# 20_Torq.net
KiCad netlist of a schematic drawn in Altium Designer
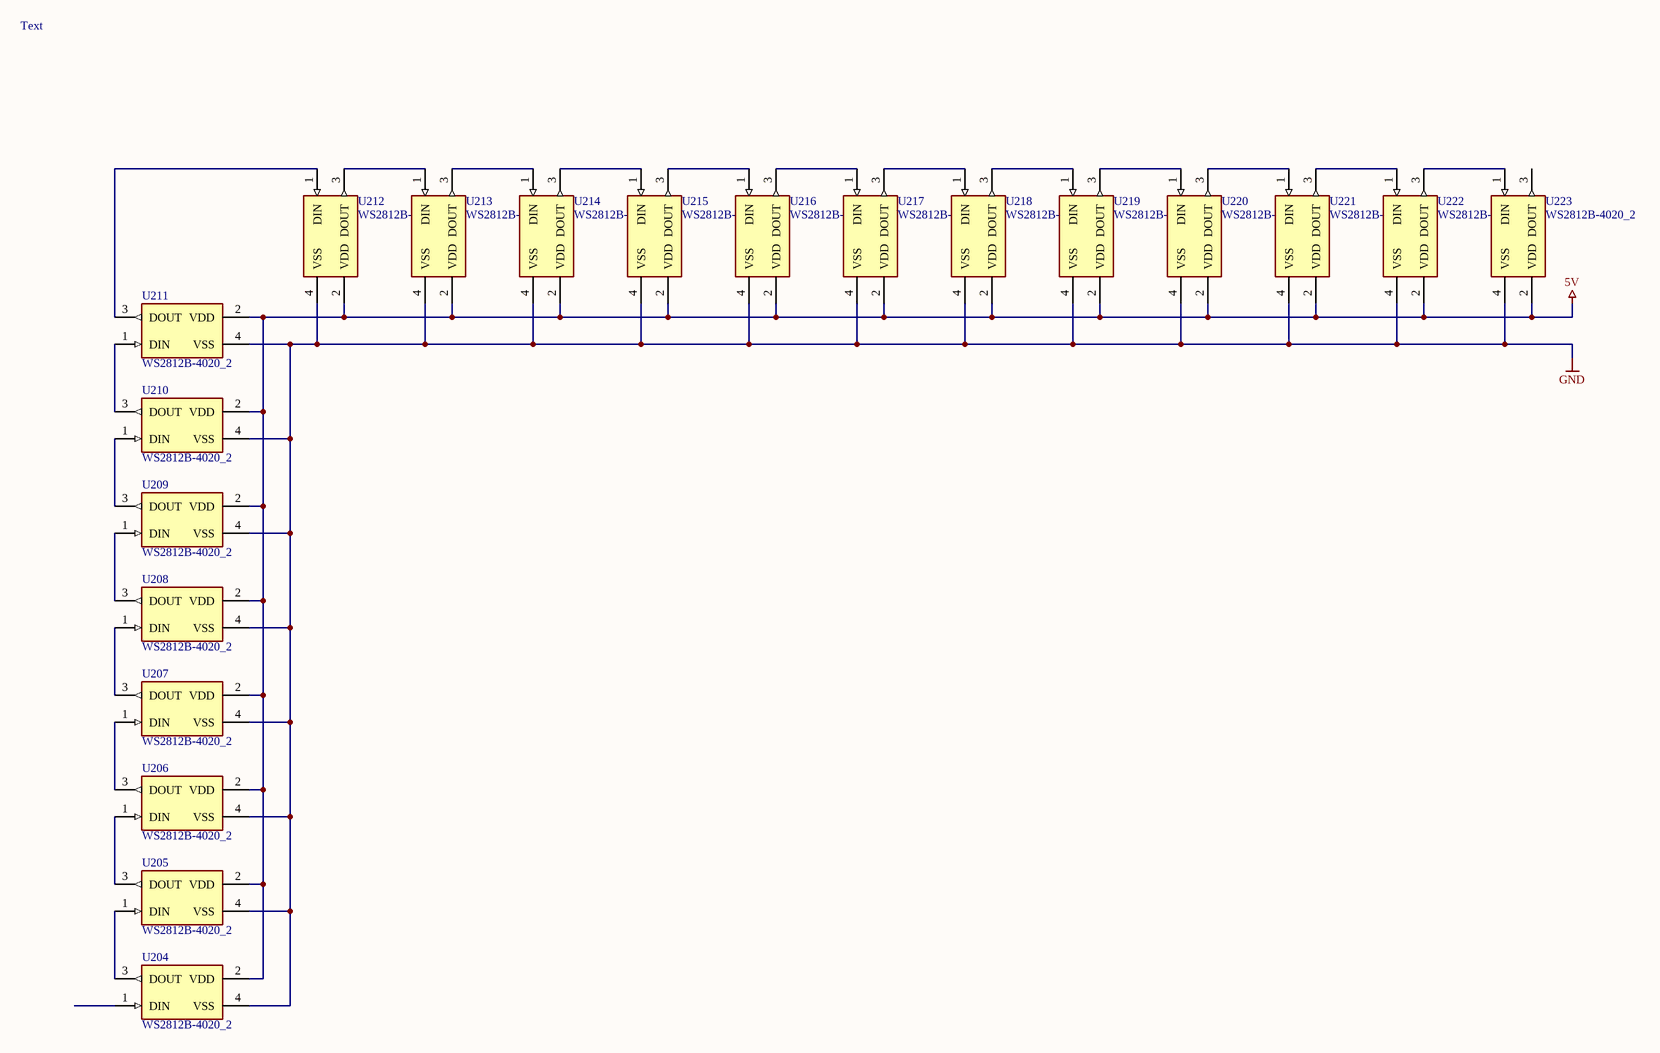
[diagram p0: 20_Torq.SchDoc]

(export (version "E")
  (design (tool "Eeschema 10.0.6"))
  (components
    (comp (ref "U204")
      (value "WS2812B-4020_2")
      (footprint "LED_WS2812B-4020")
      (description "12mA RGB SMD,2x4mm Light Emitting Diodes")
      (fields (field (name "MP") "WS2812B-4020") (field (name "MF") "Worldsemi"))
      (libsource (lib "AltiumLib_MILUTIN") (part "WS2812B-4020_2"))
    )
    (comp (ref "U205")
      (value "WS2812B-4020_2")
      (footprint "LED_WS2812B-4020")
      (description "12mA RGB SMD,2x4mm Light Emitting Diodes")
      (fields (field (name "MP") "WS2812B-4020") (field (name "MF") "Worldsemi"))
      (libsource (lib "AltiumLib_MILUTIN") (part "WS2812B-4020_2"))
    )
    (comp (ref "U206")
      (value "WS2812B-4020_2")
      (footprint "LED_WS2812B-4020")
      (description "12mA RGB SMD,2x4mm Light Emitting Diodes")
      (fields (field (name "MP") "WS2812B-4020") (field (name "MF") "Worldsemi"))
      (libsource (lib "AltiumLib_MILUTIN") (part "WS2812B-4020_2"))
    )
    (comp (ref "U207")
      (value "WS2812B-4020_2")
      (footprint "LED_WS2812B-4020")
      (description "12mA RGB SMD,2x4mm Light Emitting Diodes")
      (fields (field (name "MP") "WS2812B-4020") (field (name "MF") "Worldsemi"))
      (libsource (lib "AltiumLib_MILUTIN") (part "WS2812B-4020_2"))
    )
    (comp (ref "U208")
      (value "WS2812B-4020_2")
      (footprint "LED_WS2812B-4020")
      (description "12mA RGB SMD,2x4mm Light Emitting Diodes")
      (fields (field (name "MP") "WS2812B-4020") (field (name "MF") "Worldsemi"))
      (libsource (lib "AltiumLib_MILUTIN") (part "WS2812B-4020_2"))
    )
    (comp (ref "U209")
      (value "WS2812B-4020_2")
      (footprint "LED_WS2812B-4020")
      (description "12mA RGB SMD,2x4mm Light Emitting Diodes")
      (fields (field (name "MP") "WS2812B-4020") (field (name "MF") "Worldsemi"))
      (libsource (lib "AltiumLib_MILUTIN") (part "WS2812B-4020_2"))
    )
    (comp (ref "U210")
      (value "WS2812B-4020_2")
      (footprint "LED_WS2812B-4020")
      (description "12mA RGB SMD,2x4mm Light Emitting Diodes")
      (fields (field (name "MP") "WS2812B-4020") (field (name "MF") "Worldsemi"))
      (libsource (lib "AltiumLib_MILUTIN") (part "WS2812B-4020_2"))
    )
    (comp (ref "U211")
      (value "WS2812B-4020_2")
      (footprint "LED_WS2812B-4020")
      (description "12mA RGB SMD,2x4mm Light Emitting Diodes")
      (fields (field (name "MP") "WS2812B-4020") (field (name "MF") "Worldsemi"))
      (libsource (lib "AltiumLib_MILUTIN") (part "WS2812B-4020_2"))
    )
    (comp (ref "U212")
      (value "WS2812B-4020_2")
      (footprint "LED_WS2812B-4020")
      (description "12mA RGB SMD,2x4mm Light Emitting Diodes")
      (fields (field (name "MP") "WS2812B-4020") (field (name "MF") "Worldsemi"))
      (libsource (lib "") (part "WS2812B-4020_2_1"))
    )
    (comp (ref "U213")
      (value "WS2812B-4020_2")
      (footprint "LED_WS2812B-4020")
      (description "12mA RGB SMD,2x4mm Light Emitting Diodes")
      (fields (field (name "MP") "WS2812B-4020") (field (name "MF") "Worldsemi"))
      (libsource (lib "") (part "WS2812B-4020_2_1"))
    )
    (comp (ref "U214")
      (value "WS2812B-4020_2")
      (footprint "LED_WS2812B-4020")
      (description "12mA RGB SMD,2x4mm Light Emitting Diodes")
      (fields (field (name "MP") "WS2812B-4020") (field (name "MF") "Worldsemi"))
      (libsource (lib "") (part "WS2812B-4020_2_1"))
    )
    (comp (ref "U215")
      (value "WS2812B-4020_2")
      (footprint "LED_WS2812B-4020")
      (description "12mA RGB SMD,2x4mm Light Emitting Diodes")
      (fields (field (name "MP") "WS2812B-4020") (field (name "MF") "Worldsemi"))
      (libsource (lib "") (part "WS2812B-4020_2_1"))
    )
    (comp (ref "U216")
      (value "WS2812B-4020_2")
      (footprint "LED_WS2812B-4020")
      (description "12mA RGB SMD,2x4mm Light Emitting Diodes")
      (fields (field (name "MP") "WS2812B-4020") (field (name "MF") "Worldsemi"))
      (libsource (lib "") (part "WS2812B-4020_2_1"))
    )
    (comp (ref "U217")
      (value "WS2812B-4020_2")
      (footprint "LED_WS2812B-4020")
      (description "12mA RGB SMD,2x4mm Light Emitting Diodes")
      (fields (field (name "MP") "WS2812B-4020") (field (name "MF") "Worldsemi"))
      (libsource (lib "") (part "WS2812B-4020_2_1"))
    )
    (comp (ref "U218")
      (value "WS2812B-4020_2")
      (footprint "LED_WS2812B-4020")
      (description "12mA RGB SMD,2x4mm Light Emitting Diodes")
      (fields (field (name "MP") "WS2812B-4020") (field (name "MF") "Worldsemi"))
      (libsource (lib "") (part "WS2812B-4020_2_1"))
    )
    (comp (ref "U219")
      (value "WS2812B-4020_2")
      (footprint "LED_WS2812B-4020")
      (description "12mA RGB SMD,2x4mm Light Emitting Diodes")
      (fields (field (name "MP") "WS2812B-4020") (field (name "MF") "Worldsemi"))
      (libsource (lib "") (part "WS2812B-4020_2_1"))
    )
    (comp (ref "U220")
      (value "WS2812B-4020_2")
      (footprint "LED_WS2812B-4020")
      (description "12mA RGB SMD,2x4mm Light Emitting Diodes")
      (fields (field (name "MP") "WS2812B-4020") (field (name "MF") "Worldsemi"))
      (libsource (lib "") (part "WS2812B-4020_2_1"))
    )
    (comp (ref "U221")
      (value "WS2812B-4020_2")
      (footprint "LED_WS2812B-4020")
      (description "12mA RGB SMD,2x4mm Light Emitting Diodes")
      (fields (field (name "MP") "WS2812B-4020") (field (name "MF") "Worldsemi"))
      (libsource (lib "") (part "WS2812B-4020_2_1"))
    )
    (comp (ref "U222")
      (value "WS2812B-4020_2")
      (footprint "LED_WS2812B-4020")
      (description "12mA RGB SMD,2x4mm Light Emitting Diodes")
      (fields (field (name "MP") "WS2812B-4020") (field (name "MF") "Worldsemi"))
      (libsource (lib "") (part "WS2812B-4020_2_1"))
    )
    (comp (ref "U223")
      (value "WS2812B-4020_2")
      (footprint "LED_WS2812B-4020")
      (description "12mA RGB SMD,2x4mm Light Emitting Diodes")
      (fields (field (name "MP") "WS2812B-4020") (field (name "MF") "Worldsemi"))
      (libsource (lib "") (part "WS2812B-4020_2_1"))
    )
  )
  (nets
    (net (code "1") (name "5V") (class "Default")
      (node (ref "U204") (pin "2") (pinfunction "VDD_2") (pintype "power_in"))
      (node (ref "U205") (pin "2") (pinfunction "VDD_2") (pintype "power_in"))
      (node (ref "U206") (pin "2") (pinfunction "VDD_2") (pintype "power_in"))
      (node (ref "U207") (pin "2") (pinfunction "VDD_2") (pintype "power_in"))
      (node (ref "U208") (pin "2") (pinfunction "VDD_2") (pintype "power_in"))
      (node (ref "U209") (pin "2") (pinfunction "VDD_2") (pintype "power_in"))
      (node (ref "U210") (pin "2") (pinfunction "VDD_2") (pintype "power_in"))
      (node (ref "U211") (pin "2") (pinfunction "VDD_2") (pintype "power_in"))
      (node (ref "U212") (pin "2") (pinfunction "VDD_2") (pintype "power_in"))
      (node (ref "U213") (pin "2") (pinfunction "VDD_2") (pintype "power_in"))
      (node (ref "U214") (pin "2") (pinfunction "VDD_2") (pintype "power_in"))
      (node (ref "U215") (pin "2") (pinfunction "VDD_2") (pintype "power_in"))
      (node (ref "U216") (pin "2") (pinfunction "VDD_2") (pintype "power_in"))
      (node (ref "U217") (pin "2") (pinfunction "VDD_2") (pintype "power_in"))
      (node (ref "U218") (pin "2") (pinfunction "VDD_2") (pintype "power_in"))
      (node (ref "U219") (pin "2") (pinfunction "VDD_2") (pintype "power_in"))
      (node (ref "U220") (pin "2") (pinfunction "VDD_2") (pintype "power_in"))
      (node (ref "U221") (pin "2") (pinfunction "VDD_2") (pintype "power_in"))
      (node (ref "U222") (pin "2") (pinfunction "VDD_2") (pintype "power_in"))
      (node (ref "U223") (pin "2") (pinfunction "VDD_2") (pintype "power_in"))
    )
    (net (code "2") (name "GND") (class "Default")
      (node (ref "U204") (pin "4") (pinfunction "VSS_4") (pintype "power_in"))
      (node (ref "U205") (pin "4") (pinfunction "VSS_4") (pintype "power_in"))
      (node (ref "U206") (pin "4") (pinfunction "VSS_4") (pintype "power_in"))
      (node (ref "U207") (pin "4") (pinfunction "VSS_4") (pintype "power_in"))
      (node (ref "U208") (pin "4") (pinfunction "VSS_4") (pintype "power_in"))
      (node (ref "U209") (pin "4") (pinfunction "VSS_4") (pintype "power_in"))
      (node (ref "U210") (pin "4") (pinfunction "VSS_4") (pintype "power_in"))
      (node (ref "U211") (pin "4") (pinfunction "VSS_4") (pintype "power_in"))
      (node (ref "U212") (pin "4") (pinfunction "VSS_4") (pintype "power_in"))
      (node (ref "U213") (pin "4") (pinfunction "VSS_4") (pintype "power_in"))
      (node (ref "U214") (pin "4") (pinfunction "VSS_4") (pintype "power_in"))
      (node (ref "U215") (pin "4") (pinfunction "VSS_4") (pintype "power_in"))
      (node (ref "U216") (pin "4") (pinfunction "VSS_4") (pintype "power_in"))
      (node (ref "U217") (pin "4") (pinfunction "VSS_4") (pintype "power_in"))
      (node (ref "U218") (pin "4") (pinfunction "VSS_4") (pintype "power_in"))
      (node (ref "U219") (pin "4") (pinfunction "VSS_4") (pintype "power_in"))
      (node (ref "U220") (pin "4") (pinfunction "VSS_4") (pintype "power_in"))
      (node (ref "U221") (pin "4") (pinfunction "VSS_4") (pintype "power_in"))
      (node (ref "U222") (pin "4") (pinfunction "VSS_4") (pintype "power_in"))
      (node (ref "U223") (pin "4") (pinfunction "VSS_4") (pintype "power_in"))
    )
    (net (code "3") (name "Net-(U204-DOUT)") (class "Default")
      (node (ref "U204") (pin "3") (pinfunction "DOUT_3") (pintype "output"))
      (node (ref "U205") (pin "1") (pinfunction "DIN_1") (pintype "input"))
    )
    (net (code "4") (name "Net-(U205-DOUT)") (class "Default")
      (node (ref "U205") (pin "3") (pinfunction "DOUT_3") (pintype "output"))
      (node (ref "U206") (pin "1") (pinfunction "DIN_1") (pintype "input"))
    )
    (net (code "5") (name "Net-(U206-DOUT)") (class "Default")
      (node (ref "U206") (pin "3") (pinfunction "DOUT_3") (pintype "output"))
      (node (ref "U207") (pin "1") (pinfunction "DIN_1") (pintype "input"))
    )
    (net (code "6") (name "Net-(U207-DOUT)") (class "Default")
      (node (ref "U207") (pin "3") (pinfunction "DOUT_3") (pintype "output"))
      (node (ref "U208") (pin "1") (pinfunction "DIN_1") (pintype "input"))
    )
    (net (code "7") (name "Net-(U208-DOUT)") (class "Default")
      (node (ref "U208") (pin "3") (pinfunction "DOUT_3") (pintype "output"))
      (node (ref "U209") (pin "1") (pinfunction "DIN_1") (pintype "input"))
    )
    (net (code "8") (name "Net-(U209-DOUT)") (class "Default")
      (node (ref "U209") (pin "3") (pinfunction "DOUT_3") (pintype "output"))
      (node (ref "U210") (pin "1") (pinfunction "DIN_1") (pintype "input"))
    )
    (net (code "9") (name "Net-(U210-DOUT)") (class "Default")
      (node (ref "U210") (pin "3") (pinfunction "DOUT_3") (pintype "output"))
      (node (ref "U211") (pin "1") (pinfunction "DIN_1") (pintype "input"))
    )
    (net (code "10") (name "Net-(U211-DOUT)") (class "Default")
      (node (ref "U211") (pin "3") (pinfunction "DOUT_3") (pintype "output"))
      (node (ref "U212") (pin "1") (pinfunction "DIN_1") (pintype "input"))
    )
    (net (code "11") (name "Net-(U212-DOUT)") (class "Default")
      (node (ref "U212") (pin "3") (pinfunction "DOUT_3") (pintype "output"))
      (node (ref "U213") (pin "1") (pinfunction "DIN_1") (pintype "input"))
    )
    (net (code "12") (name "Net-(U213-DOUT)") (class "Default")
      (node (ref "U213") (pin "3") (pinfunction "DOUT_3") (pintype "output"))
      (node (ref "U214") (pin "1") (pinfunction "DIN_1") (pintype "input"))
    )
    (net (code "13") (name "Net-(U214-DOUT)") (class "Default")
      (node (ref "U214") (pin "3") (pinfunction "DOUT_3") (pintype "output"))
      (node (ref "U215") (pin "1") (pinfunction "DIN_1") (pintype "input"))
    )
    (net (code "14") (name "Net-(U215-DOUT)") (class "Default")
      (node (ref "U215") (pin "3") (pinfunction "DOUT_3") (pintype "output"))
      (node (ref "U216") (pin "1") (pinfunction "DIN_1") (pintype "input"))
    )
    (net (code "15") (name "Net-(U216-DOUT)") (class "Default")
      (node (ref "U216") (pin "3") (pinfunction "DOUT_3") (pintype "output"))
      (node (ref "U217") (pin "1") (pinfunction "DIN_1") (pintype "input"))
    )
    (net (code "16") (name "Net-(U217-DOUT)") (class "Default")
      (node (ref "U217") (pin "3") (pinfunction "DOUT_3") (pintype "output"))
      (node (ref "U218") (pin "1") (pinfunction "DIN_1") (pintype "input"))
    )
    (net (code "17") (name "Net-(U218-DOUT)") (class "Default")
      (node (ref "U218") (pin "3") (pinfunction "DOUT_3") (pintype "output"))
      (node (ref "U219") (pin "1") (pinfunction "DIN_1") (pintype "input"))
    )
    (net (code "18") (name "Net-(U219-DOUT)") (class "Default")
      (node (ref "U219") (pin "3") (pinfunction "DOUT_3") (pintype "output"))
      (node (ref "U220") (pin "1") (pinfunction "DIN_1") (pintype "input"))
    )
    (net (code "19") (name "Net-(U220-DOUT)") (class "Default")
      (node (ref "U220") (pin "3") (pinfunction "DOUT_3") (pintype "output"))
      (node (ref "U221") (pin "1") (pinfunction "DIN_1") (pintype "input"))
    )
    (net (code "20") (name "Net-(U221-DOUT)") (class "Default")
      (node (ref "U221") (pin "3") (pinfunction "DOUT_3") (pintype "output"))
      (node (ref "U222") (pin "1") (pinfunction "DIN_1") (pintype "input"))
    )
    (net (code "21") (name "Net-(U222-DOUT)") (class "Default")
      (node (ref "U222") (pin "3") (pinfunction "DOUT_3") (pintype "output"))
      (node (ref "U223") (pin "1") (pinfunction "DIN_1") (pintype "input"))
    )
    (net (code "22") (name "unconnected-(U204-DIN-Pad1)") (class "Default")
      (node (ref "U204") (pin "1") (pinfunction "DIN_1") (pintype "input"))
    )
    (net (code "23") (name "unconnected-(U223-DOUT-Pad3)") (class "Default")
      (node (ref "U223") (pin "3") (pinfunction "DOUT_3") (pintype "output"))
    )
  )
)
